# ingress.net
KiCad netlist of a schematic drawn in Altium Designer
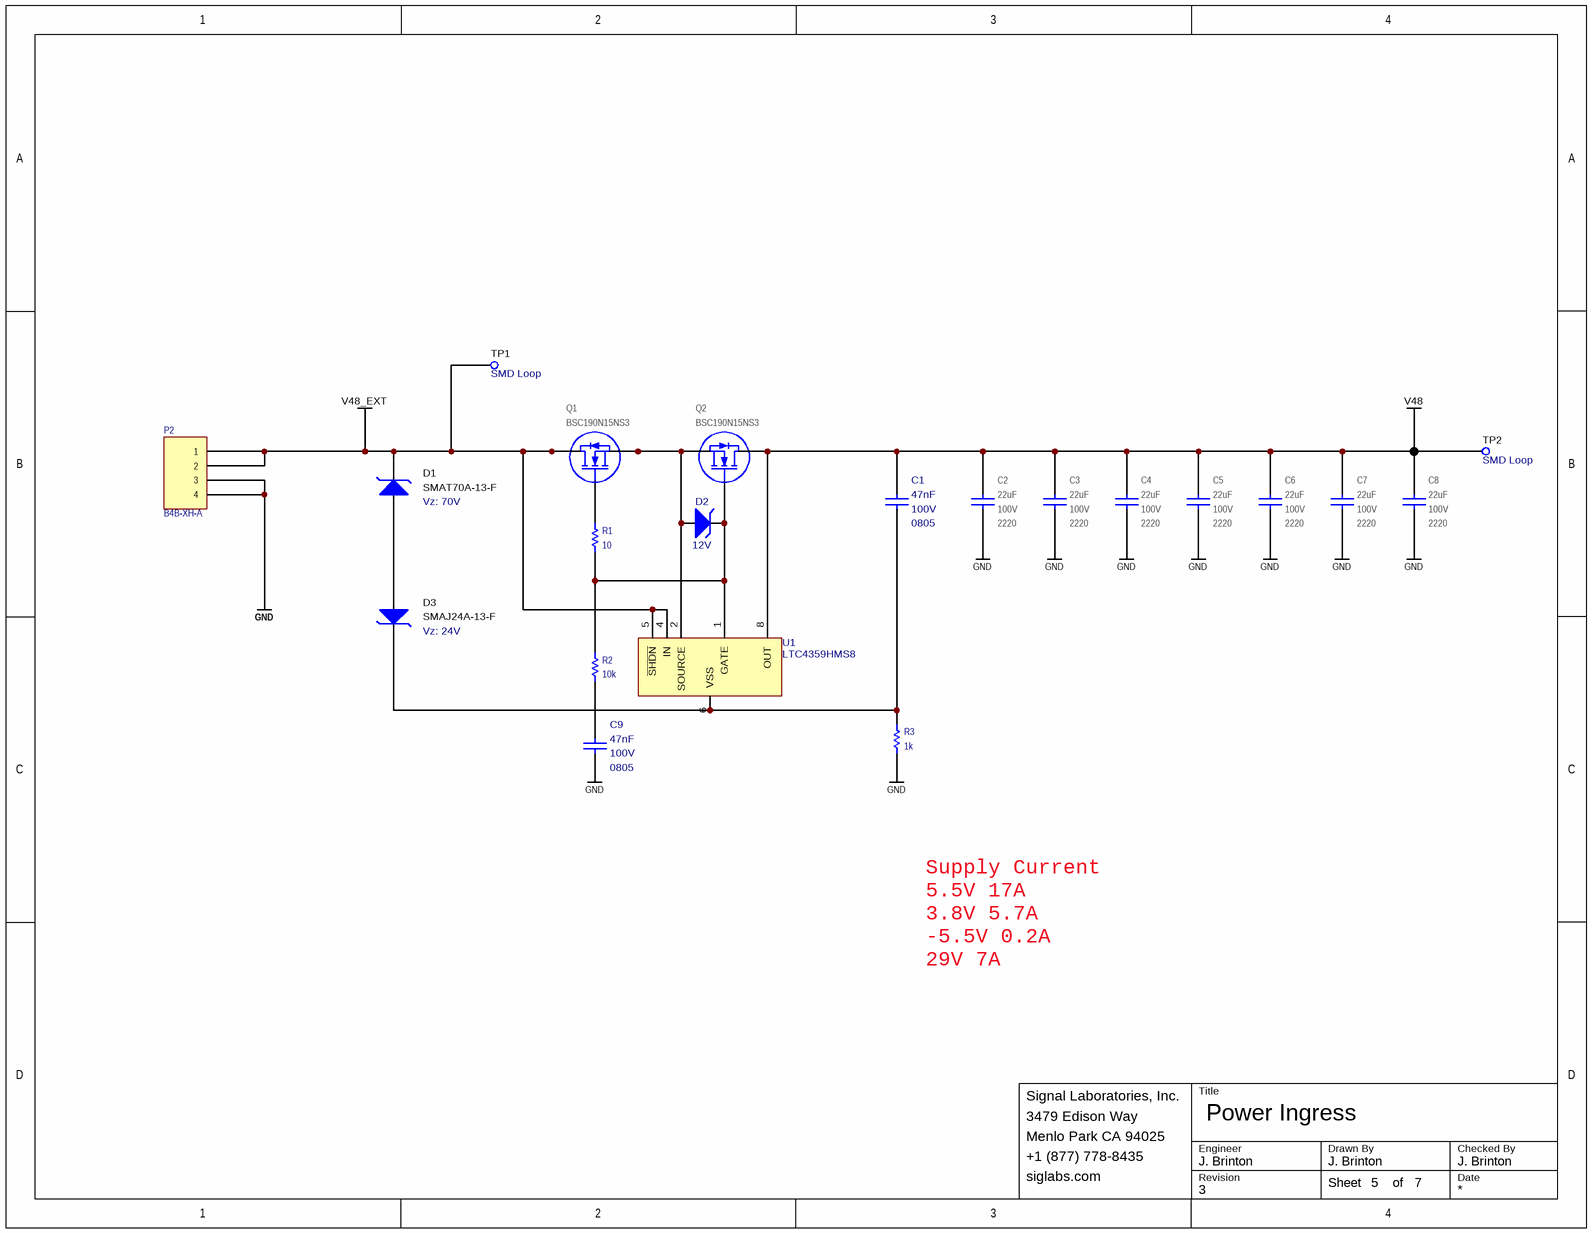
[diagram p0: ingress.SchDoc]

(export (version "E")
  (design (tool "Eeschema 10.0.6"))
  (components
    (comp (ref "C1")
      (value "47nF")
      (footprint "CAPC200X125X145L45N")
      (description "Ceramic Capacitor 47nF ±10% 100V X7R 0805")
      (fields
        (field (name "MANUFACTURER") "Vishay")
        (field (name "TOLERANCE") "±10%")
        (field (name "PACKAGE") "0805")
        (field (name "VOLTAGE") "100V")
      )
      (libsource (lib "capacitors") (part "CAP"))
    )
    (comp (ref "C2")
      (value "22uF")
      (footprint "CAPC600X500X500L160N")
      (description "Ceramic Capacitor 22uF ±20% 100V X7S Stacked")
      (fields
        (field (name "MANUFACTURER") "TDK")
        (field (name "TOLERANCE") "±20%")
        (field (name "VOLTAGE") "100V")
        (field (name "PACKAGE") "2220")
      )
      (libsource (lib "generic") (part "CAP"))
    )
    (comp (ref "C3")
      (value "22uF")
      (footprint "CAPC600X500X500L160N")
      (description "Ceramic Capacitor 22uF ±20% 100V X7S Stacked")
      (fields
        (field (name "MANUFACTURER") "TDK")
        (field (name "TOLERANCE") "±20%")
        (field (name "VOLTAGE") "100V")
        (field (name "PACKAGE") "2220")
      )
      (libsource (lib "generic") (part "CAP"))
    )
    (comp (ref "C4")
      (value "22uF")
      (footprint "CAPC600X500X500L160N")
      (description "Ceramic Capacitor 22uF ±20% 100V X7S Stacked")
      (fields
        (field (name "MANUFACTURER") "TDK")
        (field (name "TOLERANCE") "±20%")
        (field (name "VOLTAGE") "100V")
        (field (name "PACKAGE") "2220")
      )
      (libsource (lib "generic") (part "CAP"))
    )
    (comp (ref "C5")
      (value "22uF")
      (footprint "CAPC600X500X500L160N")
      (description "Ceramic Capacitor 22uF ±20% 100V X7S Stacked")
      (fields
        (field (name "MANUFACTURER") "TDK")
        (field (name "TOLERANCE") "±20%")
        (field (name "VOLTAGE") "100V")
        (field (name "PACKAGE") "2220")
      )
      (libsource (lib "generic") (part "CAP"))
    )
    (comp (ref "C6")
      (value "22uF")
      (footprint "CAPC600X500X500L160N")
      (description "Ceramic Capacitor 22uF ±20% 100V X7S Stacked")
      (fields
        (field (name "MANUFACTURER") "TDK")
        (field (name "TOLERANCE") "±20%")
        (field (name "VOLTAGE") "100V")
        (field (name "PACKAGE") "2220")
      )
      (libsource (lib "generic") (part "CAP"))
    )
    (comp (ref "C7")
      (value "22uF")
      (footprint "CAPC600X500X500L160N")
      (description "Ceramic Capacitor 22uF ±20% 100V X7S Stacked")
      (fields
        (field (name "MANUFACTURER") "TDK")
        (field (name "TOLERANCE") "±20%")
        (field (name "VOLTAGE") "100V")
        (field (name "PACKAGE") "2220")
      )
      (libsource (lib "generic") (part "CAP"))
    )
    (comp (ref "C8")
      (value "22uF")
      (footprint "CAPC600X500X500L160N")
      (description "Ceramic Capacitor 22uF ±20% 100V X7S Stacked")
      (fields
        (field (name "MANUFACTURER") "TDK")
        (field (name "TOLERANCE") "±20%")
        (field (name "VOLTAGE") "100V")
        (field (name "PACKAGE") "2220")
      )
      (libsource (lib "generic") (part "CAP"))
    )
    (comp (ref "C9")
      (value "47nF")
      (footprint "CAPC200X125X145L45N")
      (description "Ceramic Capacitor 47nF ±10% 100V X7R 0805")
      (fields
        (field (name "MANUFACTURER") "Vishay")
        (field (name "TOLERANCE") "±10%")
        (field (name "PACKAGE") "0805")
        (field (name "VOLTAGE") "100V")
      )
      (libsource (lib "capacitors") (part "CAP"))
    )
    (comp (ref "D1")
      (value "SMAT70A-13-F")
      (footprint "SMA")
      (description "TVS Diode 70V/100V SMA")
      (fields (field (name "MANUFACTURER") "Diodes Inc") (field (name "VZ") "70V"))
      (libsource (lib "generic") (part "TVS"))
    )
    (comp (ref "D2")
      (value "DDZ12BQ-7")
      (footprint "SOD123")
      (description "Zener Diode 12V 370mW SOD123")
      (fields (field (name "MANUFACTURER") "Diodes Inc") (field (name "VZ") "12V"))
      (libsource (lib "generic") (part "ZENER"))
    )
    (comp (ref "D3")
      (value "SMAJ24A-13-F")
      (footprint "SMA")
      (description "TVS Diode 24V/38.9V SMA")
      (fields (field (name "MANUFACTURER") "Diodes Inc") (field (name "VZ") "24V"))
      (libsource (lib "generic") (part "TVS"))
    )
    (comp (ref "P2")
      (value "B4B-XH-A")
      (footprint "jst:B4B-XH-A")
      (description "2.5mm pitch 4-position connector")
      (fields (field (name "MANUFACTURER") "JST"))
      (libsource (lib "jst") (part "S4B-XH-A"))
    )
    (comp (ref "Q1")
      (value "BSC190N15NS3")
      (footprint "TDSON-8")
      (description "MOSFET N-Channel Enhancement Mode")
      (fields (field (name "MANUFACTURER") "Infineon"))
      (libsource (lib "infinion") (part "BSC190N15NS3"))
    )
    (comp (ref "Q2")
      (value "BSC190N15NS3")
      (footprint "TDSON-8")
      (description "MOSFET N-Channel Enhancement Mode")
      (fields (field (name "MANUFACTURER") "Infineon"))
      (libsource (lib "infinion") (part "BSC190N15NS3"))
    )
    (comp (ref "R1")
      (value "10")
      (footprint "RESC1005X40N")
      (description "Thin Film Resistor 10 Ohm ±1% 0402")
      (fields (field (name "TOLERANCE") "±1%") (field (name "MANUFACTURER") "Vishay"))
      (libsource (lib "generic") (part "RES"))
    )
    (comp (ref "R2")
      (value "10k")
      (footprint "RESC2012X70N")
      (description "Thin Film Resistor 10k +/-1% SMD 0805")
      (fields (field (name "TOLERANCE") "±1%") (field (name "MANUFACTURER") "Yageo"))
      (libsource (lib "generic") (part "RES"))
    )
    (comp (ref "R3")
      (value "1k")
      (footprint "RESC2012X70N")
      (description "Thin Film Resistor 1k +/-1% SMD 0805")
      (fields (field (name "TOLERANCE") "±1%") (field (name "MANUFACTURER") "Yageo"))
      (libsource (lib "generic") (part "RES"))
    )
    (comp (ref "TP1")
      (value "5015")
      (footprint "keystone:5015")
      (description "Test Point SMD")
      (fields (field (name "MANUFACTURER") "Keystone") (field (name "NOTES") "SMD Loop"))
      (libsource (lib "generic") (part "TEST_POINT_SMD_50"))
    )
    (comp (ref "TP2")
      (value "5015")
      (footprint "keystone:5015")
      (description "Test Point SMD")
      (fields (field (name "MANUFACTURER") "Keystone") (field (name "NOTES") "SMD Loop"))
      (libsource (lib "generic") (part "TEST_POINT_SMD_50"))
    )
    (comp (ref "U1")
      (value "LTC4359HMS8")
      (footprint "generic:MSOP8")
      (description "Ideal Diode Controller")
      (fields (field (name "MANUFACTURER") "Linear Technology"))
      (libsource (lib "linear") (part "LTC4359HMS8"))
    )
  )
  (nets
    (net (code "1") (name "GND") (class "Default")
      (node (ref "C2") (pin "1") (pinfunction "1_1") (pintype "passive"))
      (node (ref "C3") (pin "1") (pinfunction "1_1") (pintype "passive"))
      (node (ref "C4") (pin "1") (pinfunction "1_1") (pintype "passive"))
      (node (ref "C5") (pin "1") (pinfunction "1_1") (pintype "passive"))
      (node (ref "C6") (pin "1") (pinfunction "1_1") (pintype "passive"))
      (node (ref "C7") (pin "1") (pinfunction "1_1") (pintype "passive"))
      (node (ref "C8") (pin "1") (pinfunction "1_1") (pintype "passive"))
      (node (ref "C9") (pin "2") (pinfunction "2_2") (pintype "passive"))
      (node (ref "P2") (pin "3") (pinfunction "3_3") (pintype "passive"))
      (node (ref "P2") (pin "4") (pinfunction "4_4") (pintype "passive"))
      (node (ref "R3") (pin "1") (pinfunction "1_1") (pintype "passive"))
    )
    (net (code "2") (name "Net-(C9-Pad1)") (class "Default")
      (node (ref "C9") (pin "1") (pinfunction "1_1") (pintype "passive"))
      (node (ref "R2") (pin "1") (pinfunction "1_1") (pintype "passive"))
    )
    (net (code "3") (name "Net-(D1-A)") (class "Default")
      (node (ref "D1") (pin "1") (pinfunction "A_1") (pintype "power_in"))
      (node (ref "D3") (pin "1") (pinfunction "A_1") (pintype "power_in"))
    )
    (net (code "4") (name "Net-(D2-A)") (class "Default")
      (node (ref "D2") (pin "1") (pinfunction "A_1") (pintype "power_in"))
      (node (ref "Q1") (pin "1") (pinfunction "S_1") (pintype "passive"))
      (node (ref "Q1") (pin "2") (pinfunction "S_2") (pintype "passive"))
      (node (ref "Q1") (pin "3") (pinfunction "S_3") (pintype "passive"))
      (node (ref "Q2") (pin "1") (pinfunction "S_1") (pintype "passive"))
      (node (ref "Q2") (pin "2") (pinfunction "S_2") (pintype "passive"))
      (node (ref "Q2") (pin "3") (pinfunction "S_3") (pintype "passive"))
      (node (ref "U1") (pin "2") (pinfunction "SOURCE_2") (pintype "passive"))
    )
    (net (code "5") (name "Net-(D2-K)") (class "Default")
      (node (ref "D2") (pin "2") (pinfunction "K_2") (pintype "passive"))
      (node (ref "Q2") (pin "4") (pinfunction "G_4") (pintype "passive"))
      (node (ref "R1") (pin "1") (pinfunction "1_1") (pintype "passive"))
      (node (ref "R2") (pin "2") (pinfunction "2_2") (pintype "passive"))
      (node (ref "U1") (pin "1") (pinfunction "GATE_1") (pintype "passive"))
    )
    (net (code "6") (name "Net-(D3-K)") (class "Default")
      (node (ref "C1") (pin "2") (pinfunction "2_2") (pintype "passive"))
      (node (ref "D3") (pin "2") (pinfunction "K_2") (pintype "passive"))
      (node (ref "R3") (pin "2") (pinfunction "2_2") (pintype "passive"))
      (node (ref "U1") (pin "6") (pinfunction "VSS_6") (pintype "passive"))
    )
    (net (code "7") (name "Net-(Q1-G)") (class "Default")
      (node (ref "Q1") (pin "4") (pinfunction "G_4") (pintype "passive"))
      (node (ref "R1") (pin "2") (pinfunction "2_2") (pintype "passive"))
    )
    (net (code "8") (name "V48") (class "Default")
      (node (ref "C1") (pin "1") (pinfunction "1_1") (pintype "passive"))
      (node (ref "C2") (pin "2") (pinfunction "2_2") (pintype "passive"))
      (node (ref "C3") (pin "2") (pinfunction "2_2") (pintype "passive"))
      (node (ref "C4") (pin "2") (pinfunction "2_2") (pintype "passive"))
      (node (ref "C5") (pin "2") (pinfunction "2_2") (pintype "passive"))
      (node (ref "C6") (pin "2") (pinfunction "2_2") (pintype "passive"))
      (node (ref "C7") (pin "2") (pinfunction "2_2") (pintype "passive"))
      (node (ref "C8") (pin "2") (pinfunction "2_2") (pintype "passive"))
      (node (ref "Q2") (pin "5") (pinfunction "D_5") (pintype "passive"))
      (node (ref "Q2") (pin "6") (pinfunction "D_6") (pintype "passive"))
      (node (ref "Q2") (pin "7") (pinfunction "D_7") (pintype "passive"))
      (node (ref "Q2") (pin "8") (pinfunction "D_8") (pintype "passive"))
      (node (ref "Q2") (pin "9") (pinfunction "D_9") (pintype "passive"))
      (node (ref "TP2") (pin "1") (pinfunction "1_1") (pintype "passive"))
      (node (ref "U1") (pin "8") (pinfunction "OUT_8") (pintype "passive"))
    )
    (net (code "9") (name "V48_EXT") (class "Default")
      (node (ref "D1") (pin "2") (pinfunction "K_2") (pintype "passive"))
      (node (ref "P2") (pin "1") (pinfunction "1_1") (pintype "passive"))
      (node (ref "P2") (pin "2") (pinfunction "2_2") (pintype "passive"))
      (node (ref "Q1") (pin "5") (pinfunction "D_5") (pintype "passive"))
      (node (ref "Q1") (pin "6") (pinfunction "D_6") (pintype "passive"))
      (node (ref "Q1") (pin "7") (pinfunction "D_7") (pintype "passive"))
      (node (ref "Q1") (pin "8") (pinfunction "D_8") (pintype "passive"))
      (node (ref "Q1") (pin "9") (pinfunction "D_9") (pintype "passive"))
      (node (ref "TP1") (pin "1") (pinfunction "1_1") (pintype "passive"))
      (node (ref "U1") (pin "4") (pinfunction "IN_4") (pintype "passive"))
      (node (ref "U1") (pin "5") (pinfunction "SHDN_5") (pintype "passive"))
    )
    (net (code "10") (name "unconnected-(U1-NC-Pad3)") (class "Default")
      (node (ref "U1") (pin "3") (pinfunction "NC_3") (pintype "passive"))
    )
    (net (code "11") (name "unconnected-(U1-NC-Pad7)") (class "Default")
      (node (ref "U1") (pin "7") (pinfunction "NC_7") (pintype "passive"))
    )
  )
)
